# DarkESC.net
KiCad netlist of a schematic drawn in EAGLE
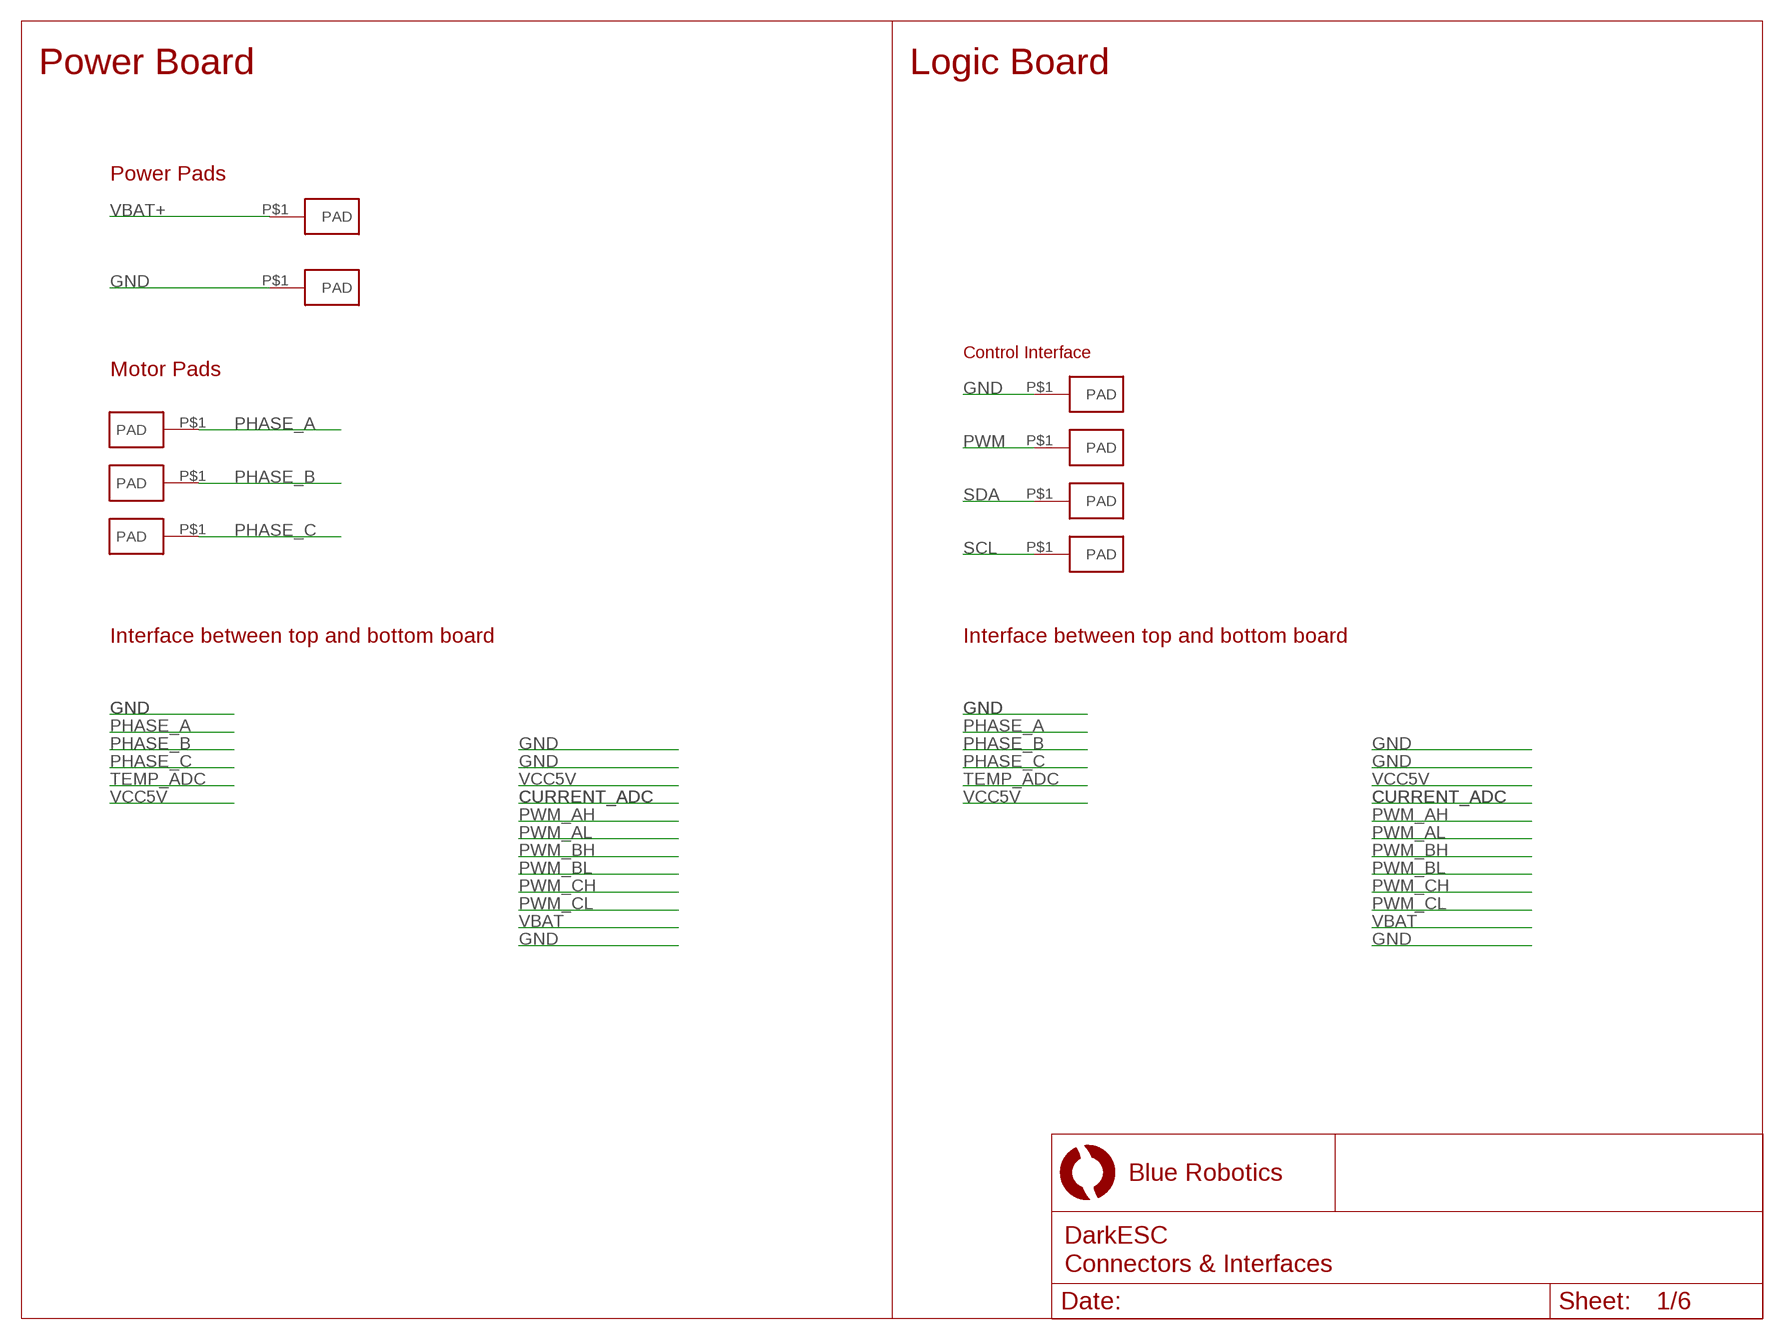
[diagram p0: schematic, sheet 1]
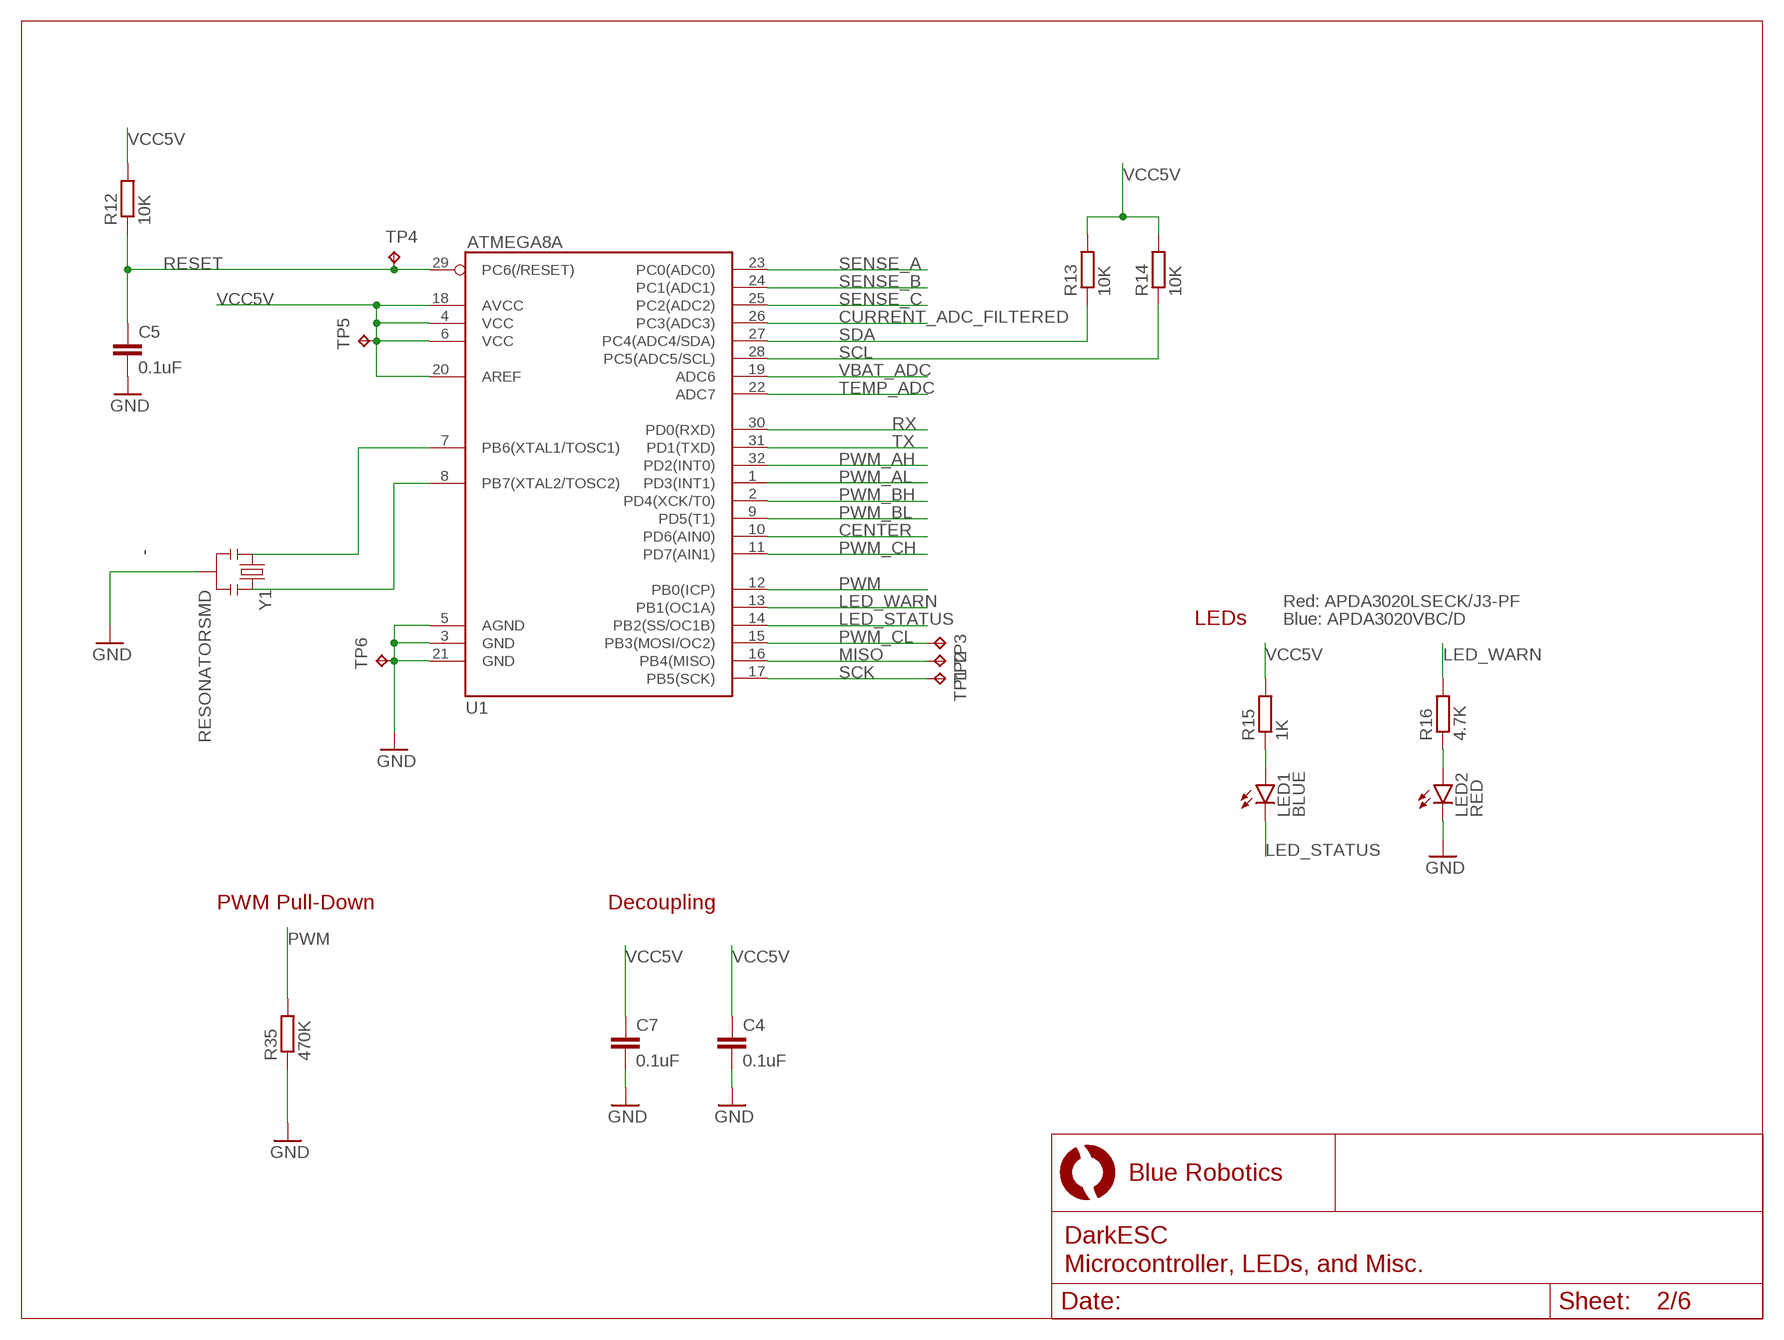
[diagram p1: schematic, sheet 2]
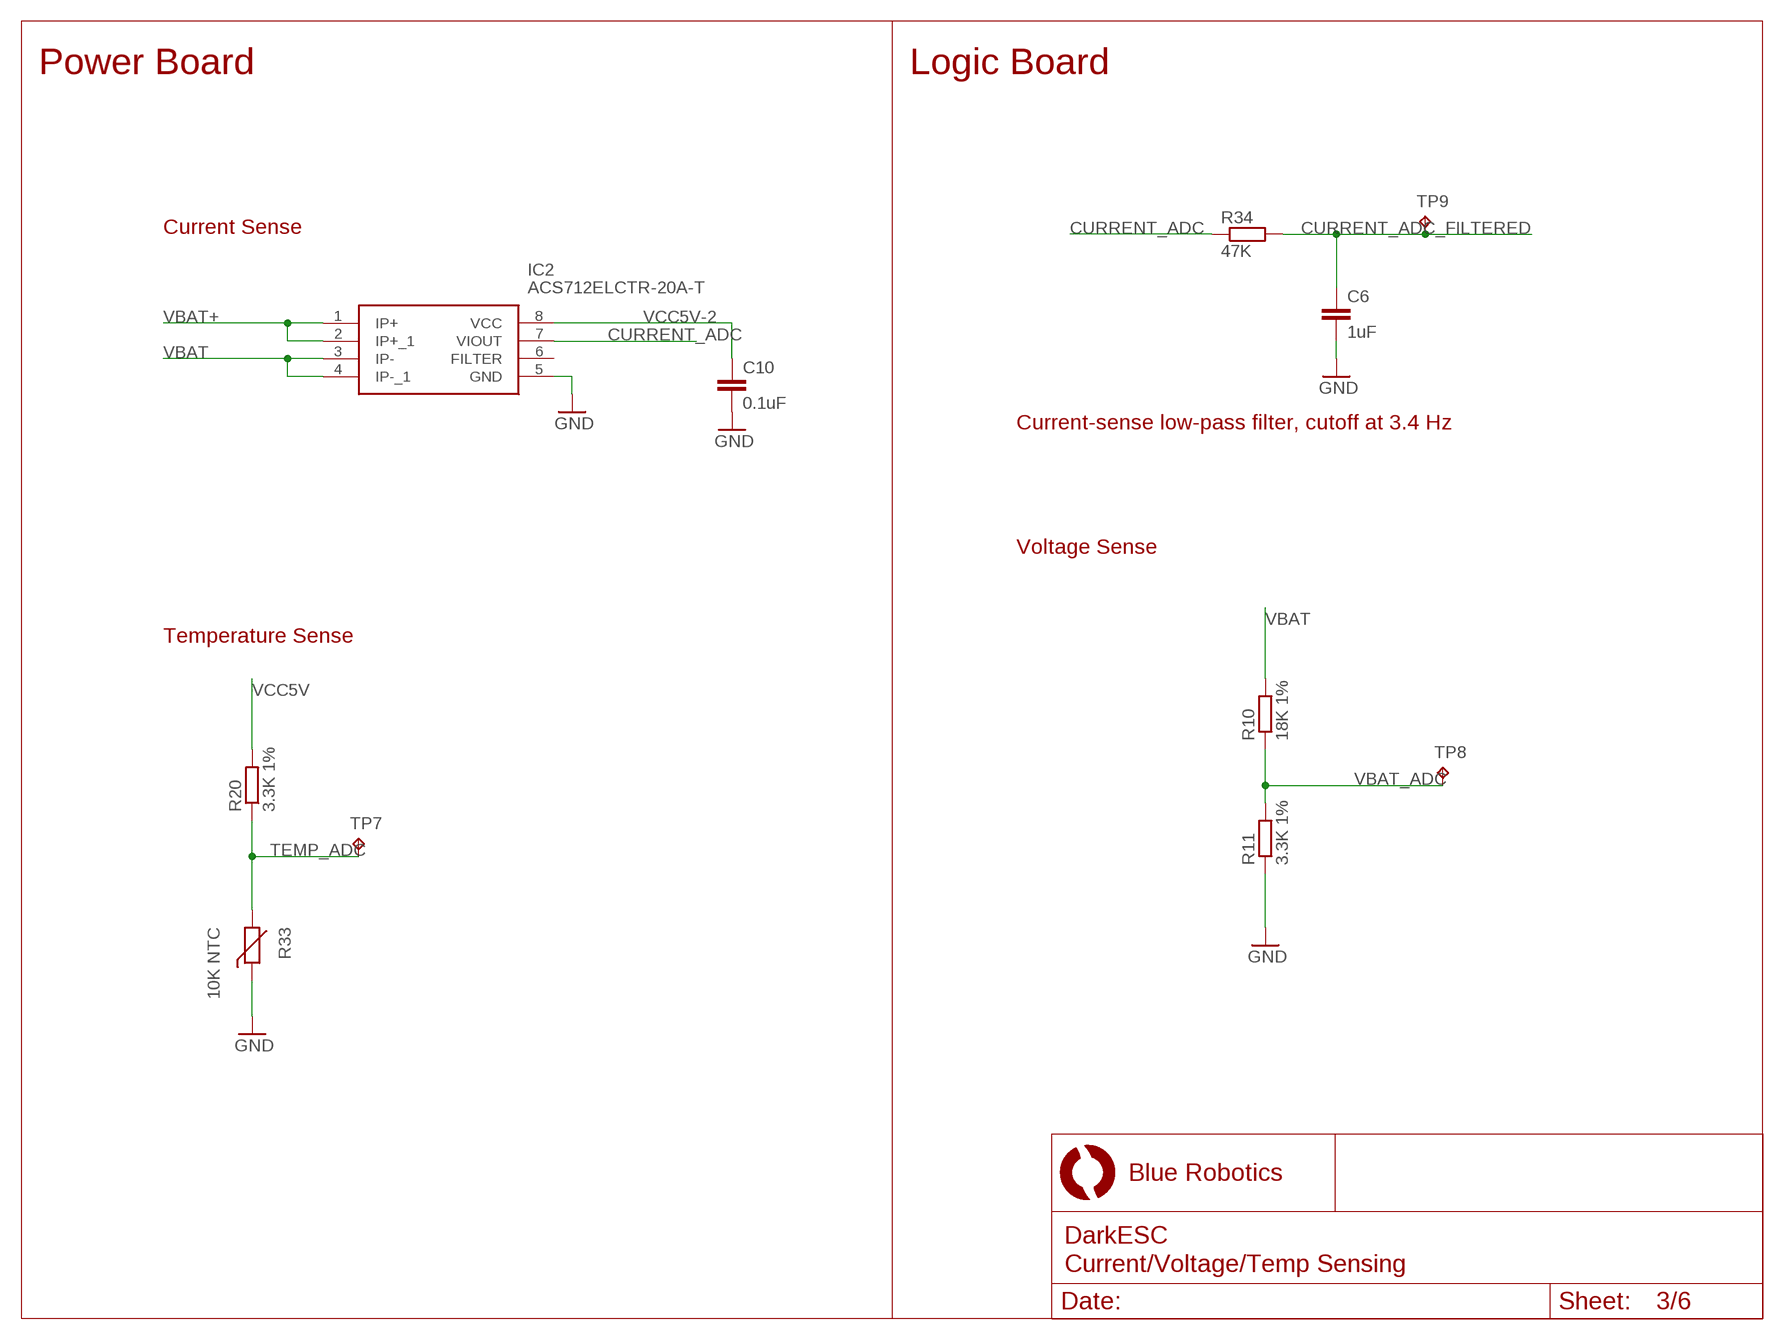
[diagram p2: schematic, sheet 3]
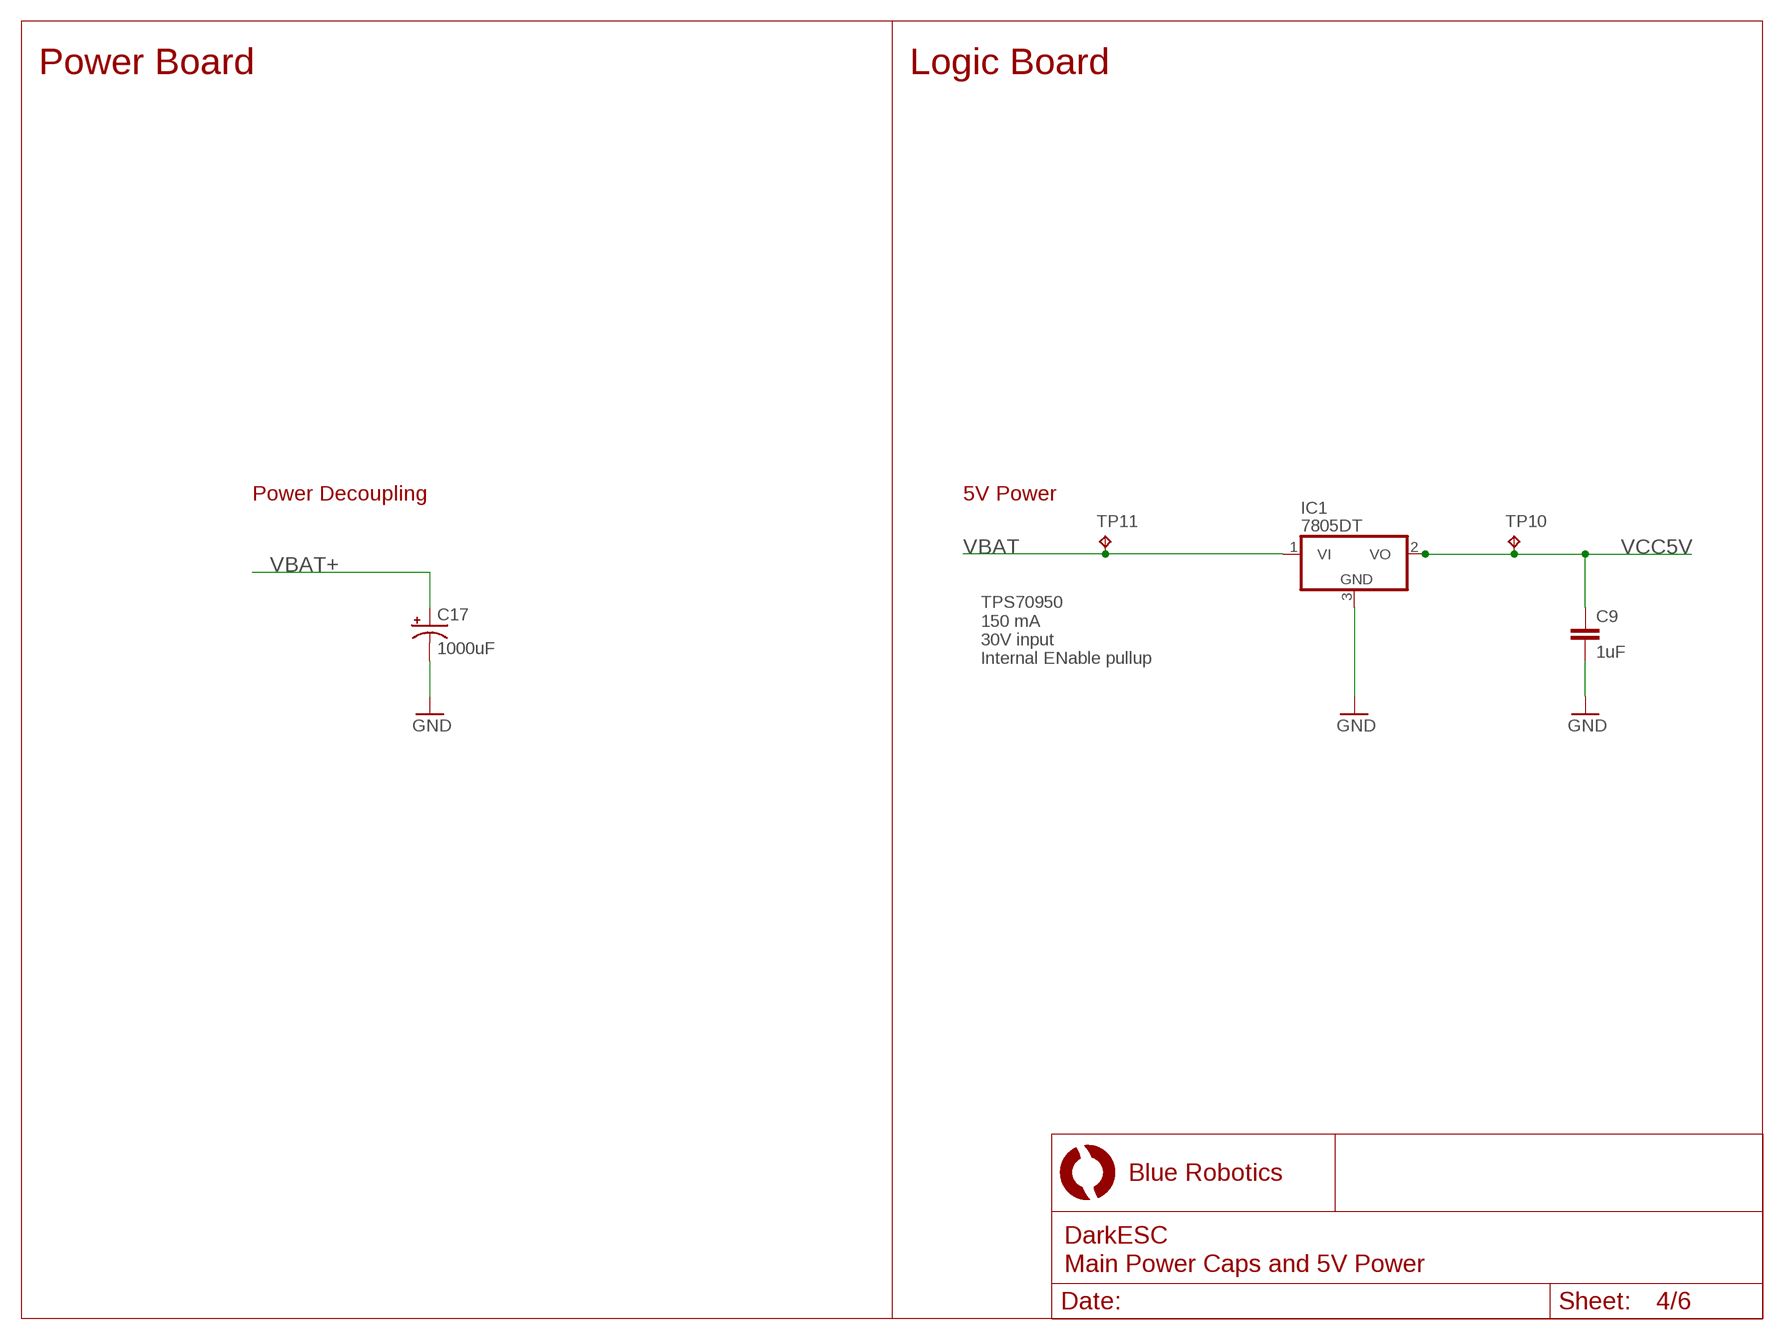
[diagram p3: schematic, sheet 4]
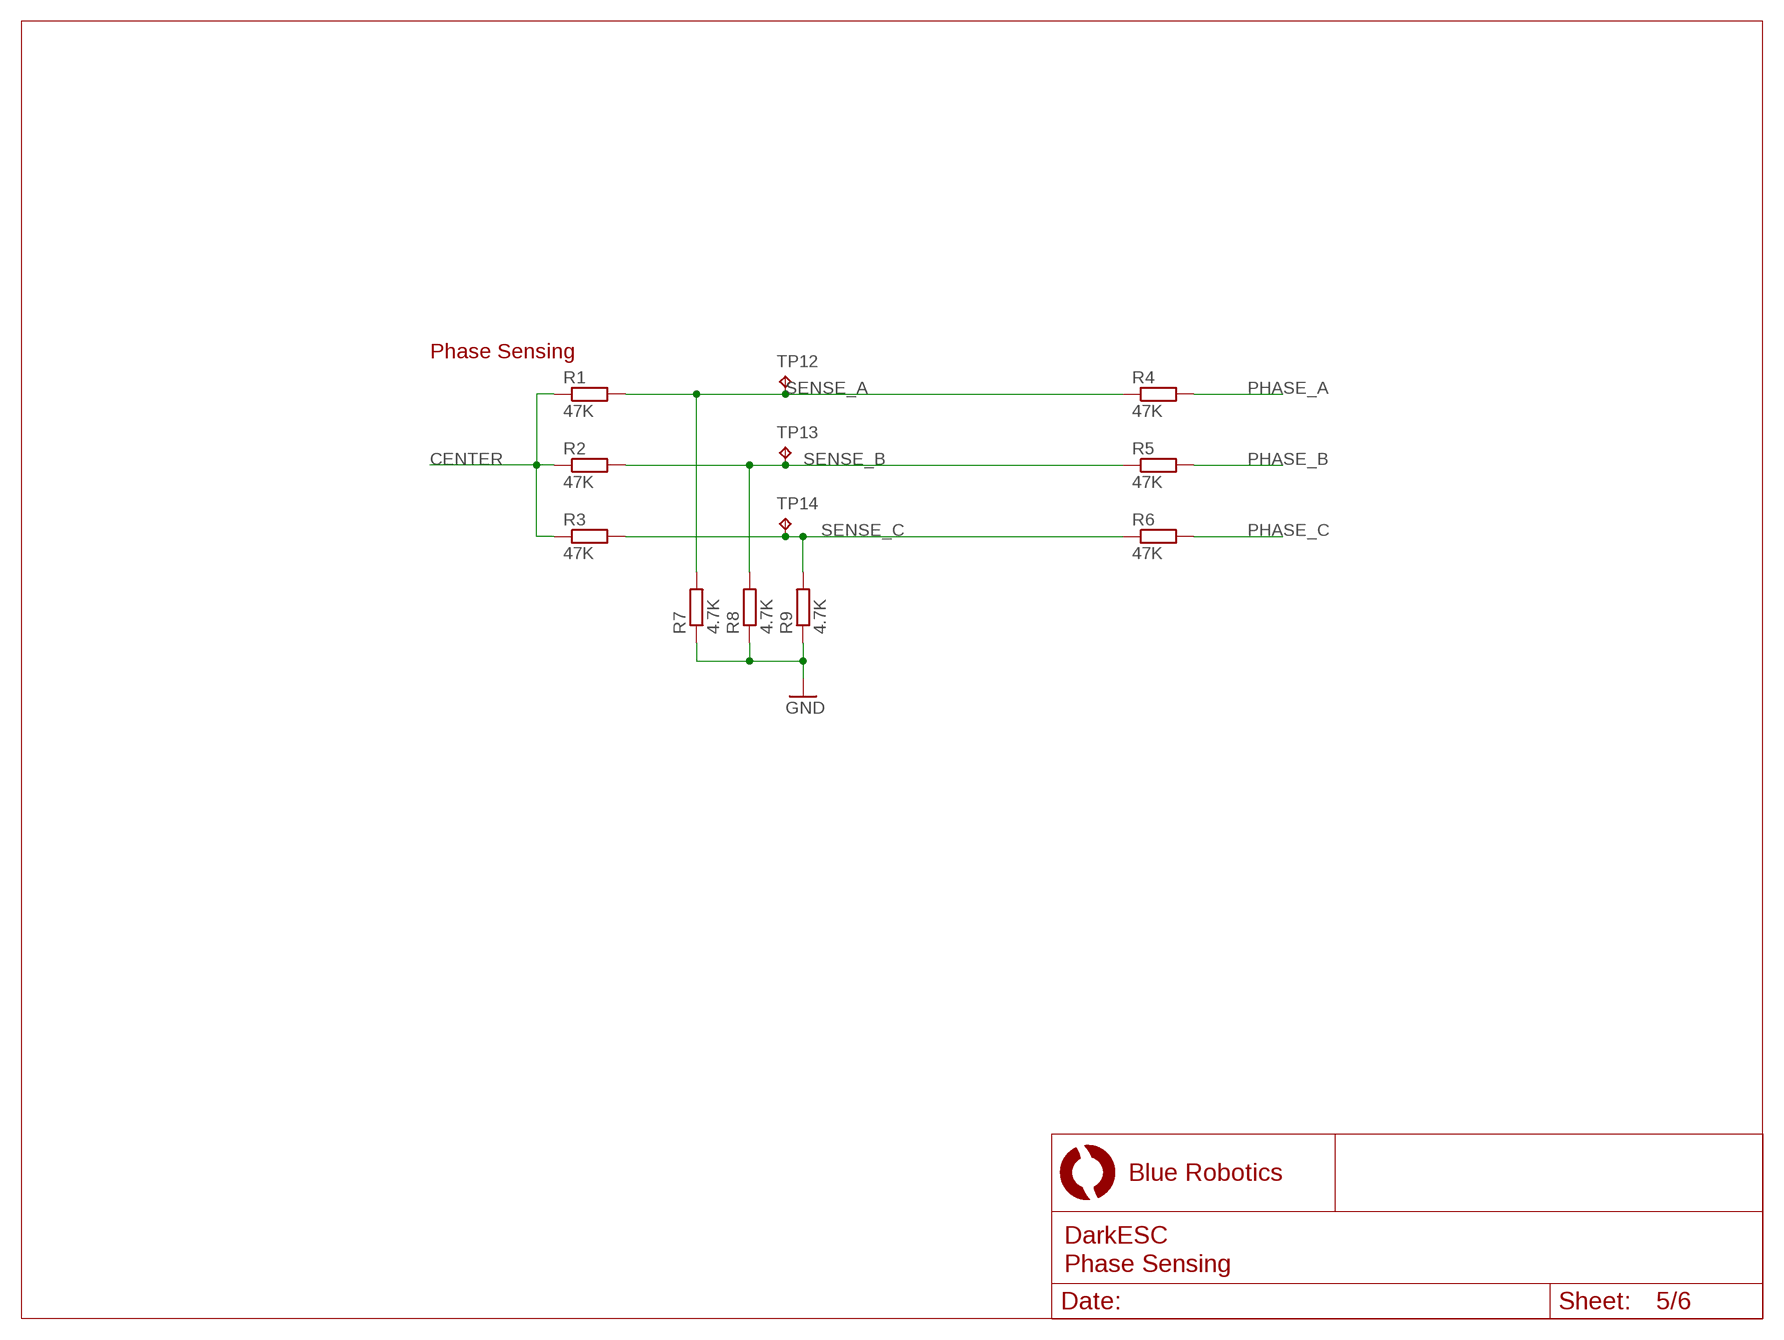
[diagram p4: schematic, sheet 5]
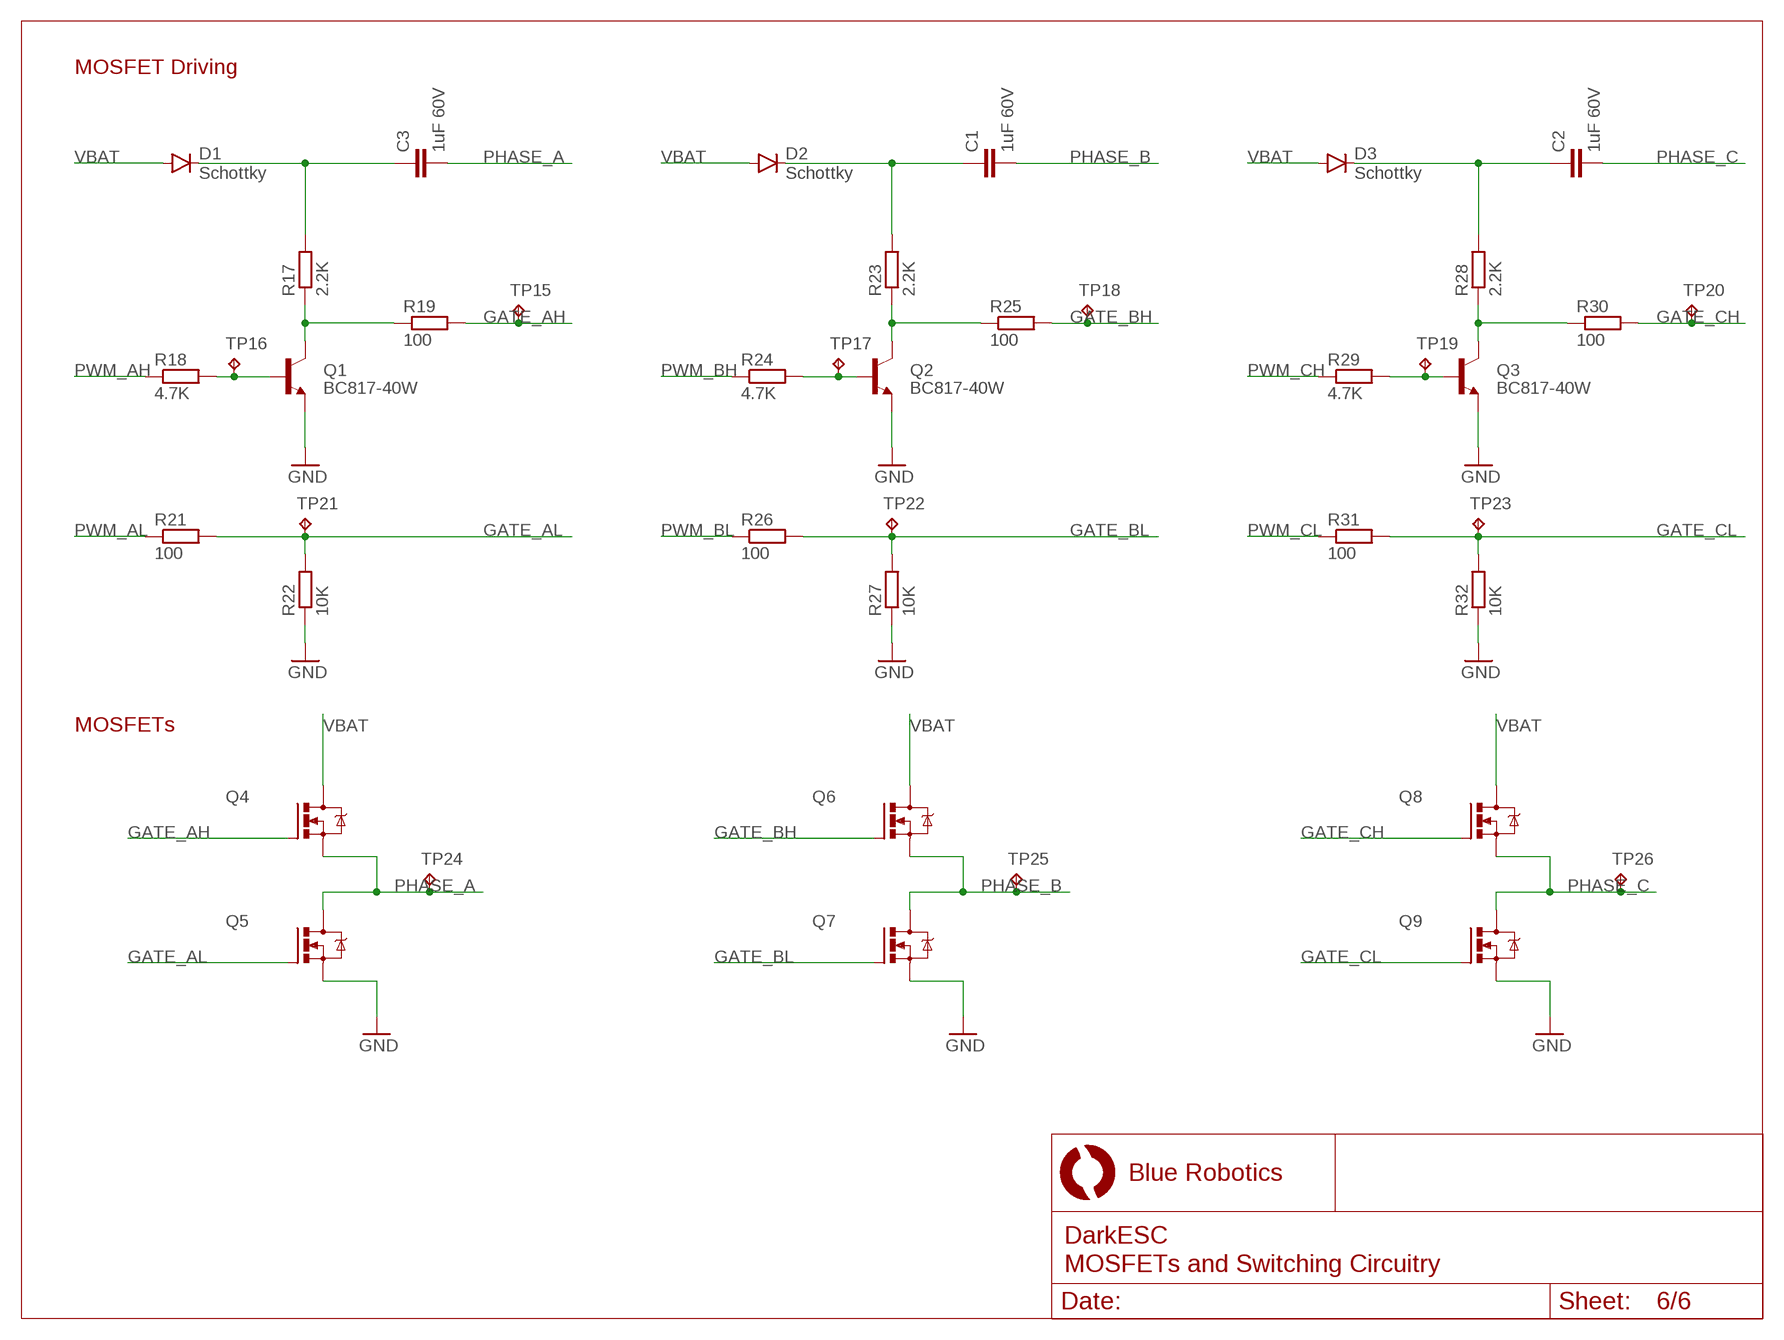
[diagram p5: schematic, sheet 6]

(export (version "E")
  (design (tool "Eeschema 10.0.6"))
  (components
    (comp (ref "C6")
      (value "1uF")
      (footprint "eagle-import:C3216")
      (libsource (lib "eagle-import") (part "C-EUC3216"))
    )
    (comp (ref "C10")
      (value "0.1uF")
      (footprint "eagle-import:C3216")
      (libsource (lib "eagle-import") (part "C-EUC3216"))
    )
    (comp (ref "IC2")
      (value "ACS712ELCTR-20A-T")
      (footprint "eagle-import:SOIC127P600X175-8N")
      (fields (field (name "RS_PART_NUMBER") "1729271"))
      (libsource (lib "eagle-import") (part "ACS712ELCTR-20A-T"))
    )
    (comp (ref "R10")
      (value "18K 1%")
      (footprint "eagle-import:0204_7")
      (libsource (lib "eagle-import") (part "R-EU_0204/7"))
    )
    (comp (ref "R11")
      (value "3.3K 1%")
      (footprint "eagle-import:0204_7")
      (libsource (lib "eagle-import") (part "R-EU_0204/7"))
    )
    (comp (ref "R20")
      (value "3.3K 1%")
      (footprint "eagle-import:0204_7")
      (libsource (lib "eagle-import") (part "R-EU_0204/7"))
    )
    (comp (ref "R33")
      (value "10K NTC")
      (footprint "eagle-import:RS-2,5")
      (libsource (lib "eagle-import") (part "THERMISTOR-2,5"))
    )
    (comp (ref "R34")
      (value "47K")
      (footprint "eagle-import:R3216")
      (libsource (lib "eagle-import") (part "R-EU_R3216"))
    )
    (comp (ref "TP7")
      (value "TPB1,27")
      (footprint "eagle-import:B1,27")
      (libsource (lib "eagle-import") (part "TPB1,27"))
    )
    (comp (ref "TP8")
      (value "TPB1,27")
      (footprint "eagle-import:B1,27")
      (libsource (lib "eagle-import") (part "TPB1,27"))
    )
    (comp (ref "TP9")
      (value "TPB1,27")
      (footprint "eagle-import:B1,27")
      (libsource (lib "eagle-import") (part "TPB1,27"))
    )
    (comp (ref "U$1")
      (value "PADPTH-MED")
      (footprint "eagle-import:PAD-PTH-MED-1")
      (libsource (lib "eagle-import") (part "PADPTH-MED"))
    )
    (comp (ref "U$2")
      (value "PADPTH-MED")
      (footprint "eagle-import:PAD-PTH-MED-1")
      (libsource (lib "eagle-import") (part "PADPTH-MED"))
    )
    (comp (ref "U$5")
      (value "PAD18AWG")
      (footprint "eagle-import:PAD-PTH-18AWG-1")
      (libsource (lib "eagle-import") (part "PAD18AWG"))
    )
    (comp (ref "U$6")
      (value "PAD18AWG")
      (footprint "eagle-import:PAD-PTH-18AWG-1")
      (libsource (lib "eagle-import") (part "PAD18AWG"))
    )
    (comp (ref "U$7")
      (value "PAD18AWG")
      (footprint "eagle-import:PAD-PTH-18AWG-1")
      (libsource (lib "eagle-import") (part "PAD18AWG"))
    )
    (comp (ref "U$11")
      (value "PAD1.5X3MM")
      (footprint "eagle-import:PAD-1.5X3MM")
      (libsource (lib "eagle-import") (part "PAD1.5X3MM"))
    )
    (comp (ref "U$12")
      (value "PAD1.5X3MM")
      (footprint "eagle-import:PAD-1.5X3MM")
      (libsource (lib "eagle-import") (part "PAD1.5X3MM"))
    )
    (comp (ref "U$13")
      (value "PAD1.5X3MM")
      (footprint "eagle-import:PAD-1.5X3MM")
      (libsource (lib "eagle-import") (part "PAD1.5X3MM"))
    )
    (comp (ref "U$14")
      (value "PAD1.5X3MM")
      (footprint "eagle-import:PAD-1.5X3MM")
      (libsource (lib "eagle-import") (part "PAD1.5X3MM"))
    )
    (comp (ref "C9")
      (value "1uF")
      (footprint "eagle-import:C3216")
      (libsource (lib "eagle-import") (part "C-EUC3216"))
    )
    (comp (ref "C17")
      (value "1000uF")
      (footprint "eagle-import:CPOL-RADIAL-100UF-25V")
      (libsource (lib "eagle-import") (part "CAP_POLPTH1"))
    )
    (comp (ref "IC1")
      (value "7805DT")
      (footprint "eagle-import:TO252")
      (libsource (lib "eagle-import") (part "78DT05"))
    )
    (comp (ref "TP10")
      (value "TPB1,27")
      (footprint "eagle-import:B1,27")
      (libsource (lib "eagle-import") (part "TPB1,27"))
    )
    (comp (ref "TP11")
      (value "TPB1,27")
      (footprint "eagle-import:B1,27")
      (libsource (lib "eagle-import") (part "TPB1,27"))
    )
    (comp (ref "R1")
      (value "47K")
      (footprint "eagle-import:R3216")
      (libsource (lib "eagle-import") (part "R-EU_R3216"))
    )
    (comp (ref "R2")
      (value "47K")
      (footprint "eagle-import:R3216")
      (libsource (lib "eagle-import") (part "R-EU_R3216"))
    )
    (comp (ref "R3")
      (value "47K")
      (footprint "eagle-import:R3216")
      (libsource (lib "eagle-import") (part "R-EU_R3216"))
    )
    (comp (ref "R4")
      (value "47K")
      (footprint "eagle-import:R3216")
      (libsource (lib "eagle-import") (part "R-EU_R3216"))
    )
    (comp (ref "R5")
      (value "47K")
      (footprint "eagle-import:R3216")
      (libsource (lib "eagle-import") (part "R-EU_R3216"))
    )
    (comp (ref "R6")
      (value "47K")
      (footprint "eagle-import:R3216")
      (libsource (lib "eagle-import") (part "R-EU_R3216"))
    )
    (comp (ref "R7")
      (value "4.7K")
      (footprint "eagle-import:R3216")
      (libsource (lib "eagle-import") (part "R-EU_R3216"))
    )
    (comp (ref "R8")
      (value "4.7K")
      (footprint "eagle-import:R3216")
      (libsource (lib "eagle-import") (part "R-EU_R3216"))
    )
    (comp (ref "R9")
      (value "4.7K")
      (footprint "eagle-import:R3216")
      (libsource (lib "eagle-import") (part "R-EU_R3216"))
    )
    (comp (ref "TP12")
      (value "TPB1,27")
      (footprint "eagle-import:B1,27")
      (libsource (lib "eagle-import") (part "TPB1,27"))
    )
    (comp (ref "TP13")
      (value "TPB1,27")
      (footprint "eagle-import:B1,27")
      (libsource (lib "eagle-import") (part "TPB1,27"))
    )
    (comp (ref "TP14")
      (value "TPB1,27")
      (footprint "eagle-import:B1,27")
      (libsource (lib "eagle-import") (part "TPB1,27"))
    )
    (comp (ref "C4")
      (value "0.1uF")
      (footprint "eagle-import:C3216")
      (libsource (lib "eagle-import") (part "C-EUC3216"))
    )
    (comp (ref "C5")
      (value "0.1uF")
      (footprint "eagle-import:C3216")
      (libsource (lib "eagle-import") (part "C-EUC3216"))
    )
    (comp (ref "C7")
      (value "0.1uF")
      (footprint "eagle-import:C3216")
      (libsource (lib "eagle-import") (part "C-EUC3216"))
    )
    (comp (ref "LED1")
      (value "BLUE")
      (footprint "eagle-import:SMT-LED-3X2-RA")
      (libsource (lib "eagle-import") (part "LED3X2-RA"))
    )
    (comp (ref "LED2")
      (value "RED")
      (footprint "eagle-import:SMT-LED-3X2-RA")
      (libsource (lib "eagle-import") (part "LED3X2-RA"))
    )
    (comp (ref "R12")
      (value "10K")
      (footprint "eagle-import:R3216")
      (libsource (lib "eagle-import") (part "R-EU_R3216"))
    )
    (comp (ref "R13")
      (value "10K")
      (footprint "eagle-import:R3216")
      (libsource (lib "eagle-import") (part "R-EU_R3216"))
    )
    (comp (ref "R14")
      (value "10K")
      (footprint "eagle-import:R3216")
      (libsource (lib "eagle-import") (part "R-EU_R3216"))
    )
    (comp (ref "R15")
      (value "1K")
      (footprint "eagle-import:R3216")
      (libsource (lib "eagle-import") (part "R-EU_R3216"))
    )
    (comp (ref "R16")
      (value "4.7K")
      (footprint "eagle-import:R3216")
      (libsource (lib "eagle-import") (part "R-EU_R3216"))
    )
    (comp (ref "R35")
      (value "470K")
      (footprint "eagle-import:R3216")
      (libsource (lib "eagle-import") (part "R-EU_R3216"))
    )
    (comp (ref "TP1")
      (value "TPB1,27")
      (footprint "eagle-import:B1,27")
      (libsource (lib "eagle-import") (part "TPB1,27"))
    )
    (comp (ref "TP2")
      (value "TPB1,27")
      (footprint "eagle-import:B1,27")
      (libsource (lib "eagle-import") (part "TPB1,27"))
    )
    (comp (ref "TP3")
      (value "TPB1,27")
      (footprint "eagle-import:B1,27")
      (libsource (lib "eagle-import") (part "TPB1,27"))
    )
    (comp (ref "TP4")
      (value "TPB1,27")
      (footprint "eagle-import:B1,27")
      (libsource (lib "eagle-import") (part "TPB1,27"))
    )
    (comp (ref "TP5")
      (value "TPB1,27")
      (footprint "eagle-import:B1,27")
      (libsource (lib "eagle-import") (part "TPB1,27"))
    )
    (comp (ref "TP6")
      (value "TPB1,27")
      (footprint "eagle-import:B1,27")
      (libsource (lib "eagle-import") (part "TPB1,27"))
    )
    (comp (ref "U1")
      (value "ATMEGA168")
      (footprint "eagle-import:TQFP32-08")
      (libsource (lib "eagle-import") (part "ATMEGA168"))
    )
    (comp (ref "Y1")
      (value "RESONATORSMD")
      (footprint "eagle-import:RESONATOR-SMD")
      (libsource (lib "eagle-import") (part "RESONATORSMD"))
    )
    (comp (ref "C1")
      (value "1uF 60V")
      (footprint "eagle-import:C3216")
      (libsource (lib "eagle-import") (part "C-EUC3216"))
    )
    (comp (ref "C2")
      (value "1uF 60V")
      (footprint "eagle-import:C3216")
      (libsource (lib "eagle-import") (part "C-EUC3216"))
    )
    (comp (ref "C3")
      (value "1uF 60V")
      (footprint "eagle-import:C3216")
      (libsource (lib "eagle-import") (part "C-EUC3216"))
    )
    (comp (ref "D1")
      (value "Schottky")
      (footprint "eagle-import:SMB-DIODE")
      (libsource (lib "eagle-import") (part "DIODESMB"))
    )
    (comp (ref "D2")
      (value "Schottky")
      (footprint "eagle-import:SMB-DIODE")
      (libsource (lib "eagle-import") (part "DIODESMB"))
    )
    (comp (ref "D3")
      (value "Schottky")
      (footprint "eagle-import:SMB-DIODE")
      (libsource (lib "eagle-import") (part "DIODESMB"))
    )
    (comp (ref "Q1")
      (value "BC817-40W")
      (footprint "eagle-import:SOT23")
      (libsource (lib "eagle-import") (part "TRANSISTOR_NPNSOT23"))
    )
    (comp (ref "Q2")
      (value "BC817-40W")
      (footprint "eagle-import:SOT23")
      (libsource (lib "eagle-import") (part "TRANSISTOR_NPNSOT23"))
    )
    (comp (ref "Q3")
      (value "BC817-40W")
      (footprint "eagle-import:SOT23")
      (libsource (lib "eagle-import") (part "TRANSISTOR_NPNSOT23"))
    )
    (comp (ref "Q4")
      (value "IRF520")
      (footprint "eagle-import:TO220BV")
      (libsource (lib "eagle-import") (part "IRF520"))
    )
    (comp (ref "Q5")
      (value "IRF520")
      (footprint "eagle-import:TO220BV")
      (libsource (lib "eagle-import") (part "IRF520"))
    )
    (comp (ref "Q6")
      (value "IRF520")
      (footprint "eagle-import:TO220BV")
      (libsource (lib "eagle-import") (part "IRF520"))
    )
    (comp (ref "Q7")
      (value "IRF520")
      (footprint "eagle-import:TO220BV")
      (libsource (lib "eagle-import") (part "IRF520"))
    )
    (comp (ref "Q8")
      (value "IRF520")
      (footprint "eagle-import:TO220BV")
      (libsource (lib "eagle-import") (part "IRF520"))
    )
    (comp (ref "Q9")
      (value "IRF520")
      (footprint "eagle-import:TO220BV")
      (libsource (lib "eagle-import") (part "IRF520"))
    )
    (comp (ref "R17")
      (value "2.2K")
      (footprint "eagle-import:R3216")
      (libsource (lib "eagle-import") (part "R-EU_R3216"))
    )
    (comp (ref "R18")
      (value "4.7K")
      (footprint "eagle-import:R3216")
      (libsource (lib "eagle-import") (part "R-EU_R3216"))
    )
    (comp (ref "R19")
      (value "100")
      (footprint "eagle-import:R3216")
      (libsource (lib "eagle-import") (part "R-EU_R3216"))
    )
    (comp (ref "R21")
      (value "100")
      (footprint "eagle-import:R3216")
      (libsource (lib "eagle-import") (part "R-EU_R3216"))
    )
    (comp (ref "R22")
      (value "10K")
      (footprint "eagle-import:R3216")
      (libsource (lib "eagle-import") (part "R-EU_R3216"))
    )
    (comp (ref "R23")
      (value "2.2K")
      (footprint "eagle-import:R3216")
      (libsource (lib "eagle-import") (part "R-EU_R3216"))
    )
    (comp (ref "R24")
      (value "4.7K")
      (footprint "eagle-import:R3216")
      (libsource (lib "eagle-import") (part "R-EU_R3216"))
    )
    (comp (ref "R25")
      (value "100")
      (footprint "eagle-import:R3216")
      (libsource (lib "eagle-import") (part "R-EU_R3216"))
    )
    (comp (ref "R26")
      (value "100")
      (footprint "eagle-import:R3216")
      (libsource (lib "eagle-import") (part "R-EU_R3216"))
    )
    (comp (ref "R27")
      (value "10K")
      (footprint "eagle-import:R3216")
      (libsource (lib "eagle-import") (part "R-EU_R3216"))
    )
    (comp (ref "R28")
      (value "2.2K")
      (footprint "eagle-import:R3216")
      (libsource (lib "eagle-import") (part "R-EU_R3216"))
    )
    (comp (ref "R29")
      (value "4.7K")
      (footprint "eagle-import:R3216")
      (libsource (lib "eagle-import") (part "R-EU_R3216"))
    )
    (comp (ref "R30")
      (value "100")
      (footprint "eagle-import:R3216")
      (libsource (lib "eagle-import") (part "R-EU_R3216"))
    )
    (comp (ref "R31")
      (value "100")
      (footprint "eagle-import:R3216")
      (libsource (lib "eagle-import") (part "R-EU_R3216"))
    )
    (comp (ref "R32")
      (value "10K")
      (footprint "eagle-import:R3216")
      (libsource (lib "eagle-import") (part "R-EU_R3216"))
    )
    (comp (ref "TP15")
      (value "TPB1,27")
      (footprint "eagle-import:B1,27")
      (libsource (lib "eagle-import") (part "TPB1,27"))
    )
    (comp (ref "TP16")
      (value "TPB1,27")
      (footprint "eagle-import:B1,27")
      (libsource (lib "eagle-import") (part "TPB1,27"))
    )
    (comp (ref "TP17")
      (value "TPB1,27")
      (footprint "eagle-import:B1,27")
      (libsource (lib "eagle-import") (part "TPB1,27"))
    )
    (comp (ref "TP18")
      (value "TPB1,27")
      (footprint "eagle-import:B1,27")
      (libsource (lib "eagle-import") (part "TPB1,27"))
    )
    (comp (ref "TP19")
      (value "TPB1,27")
      (footprint "eagle-import:B1,27")
      (libsource (lib "eagle-import") (part "TPB1,27"))
    )
    (comp (ref "TP20")
      (value "TPB1,27")
      (footprint "eagle-import:B1,27")
      (libsource (lib "eagle-import") (part "TPB1,27"))
    )
    (comp (ref "TP21")
      (value "TPB1,27")
      (footprint "eagle-import:B1,27")
      (libsource (lib "eagle-import") (part "TPB1,27"))
    )
    (comp (ref "TP22")
      (value "TPB1,27")
      (footprint "eagle-import:B1,27")
      (libsource (lib "eagle-import") (part "TPB1,27"))
    )
    (comp (ref "TP23")
      (value "TPB1,27")
      (footprint "eagle-import:B1,27")
      (libsource (lib "eagle-import") (part "TPB1,27"))
    )
    (comp (ref "TP24")
      (value "TPB1,27")
      (footprint "eagle-import:B1,27")
      (libsource (lib "eagle-import") (part "TPB1,27"))
    )
    (comp (ref "TP25")
      (value "TPB1,27")
      (footprint "eagle-import:B1,27")
      (libsource (lib "eagle-import") (part "TPB1,27"))
    )
    (comp (ref "TP26")
      (value "TPB1,27")
      (footprint "eagle-import:B1,27")
      (libsource (lib "eagle-import") (part "TPB1,27"))
    )
  )
  (nets
    (net (code "1") (name "CENTER") (class "Default")
      (node (ref "R1") (pin "1") (pinfunction "1_1") (pintype "passive"))
      (node (ref "R2") (pin "1") (pinfunction "1_1") (pintype "passive"))
      (node (ref "R3") (pin "1") (pinfunction "1_1") (pintype "passive"))
      (node (ref "U1") (pin "10") (pinfunction "PD6(AIN0)_10") (pintype "bidirectional"))
    )
    (net (code "2") (name "CURRENT_ADC") (class "Default")
      (node (ref "IC2") (pin "7") (pinfunction "VIOUT_7") (pintype "bidirectional"))
      (node (ref "R34") (pin "1") (pinfunction "1_1") (pintype "passive"))
    )
    (net (code "3") (name "CURRENT_ADC_FILTERED") (class "Default")
      (node (ref "C6") (pin "1") (pinfunction "1_1") (pintype "passive"))
      (node (ref "R34") (pin "2") (pinfunction "2_2") (pintype "passive"))
      (node (ref "TP9") (pin "TP") (pinfunction "TP_TP") (pintype "input"))
      (node (ref "U1") (pin "26") (pinfunction "PC3(ADC3)_26") (pintype "bidirectional"))
    )
    (net (code "4") (name "GATE_AH") (class "Default")
      (node (ref "Q4") (pin "G") (pinfunction "G_G") (pintype "passive"))
      (node (ref "R19") (pin "2") (pinfunction "2_2") (pintype "passive"))
      (node (ref "TP15") (pin "TP") (pinfunction "TP_TP") (pintype "input"))
    )
    (net (code "5") (name "GATE_AL") (class "Default")
      (node (ref "Q5") (pin "G") (pinfunction "G_G") (pintype "passive"))
      (node (ref "R21") (pin "2") (pinfunction "2_2") (pintype "passive"))
      (node (ref "R22") (pin "2") (pinfunction "2_2") (pintype "passive"))
      (node (ref "TP21") (pin "TP") (pinfunction "TP_TP") (pintype "input"))
    )
    (net (code "6") (name "GATE_BH") (class "Default")
      (node (ref "Q6") (pin "G") (pinfunction "G_G") (pintype "passive"))
      (node (ref "R25") (pin "2") (pinfunction "2_2") (pintype "passive"))
      (node (ref "TP18") (pin "TP") (pinfunction "TP_TP") (pintype "input"))
    )
    (net (code "7") (name "GATE_BL") (class "Default")
      (node (ref "Q7") (pin "G") (pinfunction "G_G") (pintype "passive"))
      (node (ref "R26") (pin "2") (pinfunction "2_2") (pintype "passive"))
      (node (ref "R27") (pin "2") (pinfunction "2_2") (pintype "passive"))
      (node (ref "TP22") (pin "TP") (pinfunction "TP_TP") (pintype "input"))
    )
    (net (code "8") (name "GATE_CH") (class "Default")
      (node (ref "Q8") (pin "G") (pinfunction "G_G") (pintype "passive"))
      (node (ref "R30") (pin "2") (pinfunction "2_2") (pintype "passive"))
      (node (ref "TP20") (pin "TP") (pinfunction "TP_TP") (pintype "input"))
    )
    (net (code "9") (name "GATE_CL") (class "Default")
      (node (ref "Q9") (pin "G") (pinfunction "G_G") (pintype "passive"))
      (node (ref "R31") (pin "2") (pinfunction "2_2") (pintype "passive"))
      (node (ref "R32") (pin "2") (pinfunction "2_2") (pintype "passive"))
      (node (ref "TP23") (pin "TP") (pinfunction "TP_TP") (pintype "input"))
    )
    (net (code "10") (name "GND") (class "Default")
      (node (ref "C10") (pin "2") (pinfunction "2_2") (pintype "passive"))
      (node (ref "C17") (pin "2") (pinfunction "-_2") (pintype "passive"))
      (node (ref "C4") (pin "2") (pinfunction "2_2") (pintype "passive"))
      (node (ref "C5") (pin "2") (pinfunction "2_2") (pintype "passive"))
      (node (ref "C6") (pin "2") (pinfunction "2_2") (pintype "passive"))
      (node (ref "C7") (pin "2") (pinfunction "2_2") (pintype "passive"))
      (node (ref "C9") (pin "2") (pinfunction "2_2") (pintype "passive"))
      (node (ref "IC1") (pin "3") (pinfunction "GND_3") (pintype "passive"))
      (node (ref "IC2") (pin "5") (pinfunction "GND_5") (pintype "power_in"))
      (node (ref "LED2") (pin "2") (pinfunction "C_2") (pintype "passive"))
      (node (ref "Q1") (pin "2") (pinfunction "E_2") (pintype "passive"))
      (node (ref "Q2") (pin "2") (pinfunction "E_2") (pintype "passive"))
      (node (ref "Q3") (pin "2") (pinfunction "E_2") (pintype "passive"))
      (node (ref "Q5") (pin "S") (pinfunction "S_S") (pintype "passive"))
      (node (ref "Q7") (pin "S") (pinfunction "S_S") (pintype "passive"))
      (node (ref "Q9") (pin "S") (pinfunction "S_S") (pintype "passive"))
      (node (ref "R11") (pin "1") (pinfunction "1_1") (pintype "passive"))
      (node (ref "R22") (pin "1") (pinfunction "1_1") (pintype "passive"))
      (node (ref "R27") (pin "1") (pinfunction "1_1") (pintype "passive"))
      (node (ref "R32") (pin "1") (pinfunction "1_1") (pintype "passive"))
      (node (ref "R33") (pin "1") (pinfunction "1_1") (pintype "passive"))
      (node (ref "R35") (pin "1") (pinfunction "1_1") (pintype "passive"))
      (node (ref "R7") (pin "1") (pinfunction "1_1") (pintype "passive"))
      (node (ref "R8") (pin "1") (pinfunction "1_1") (pintype "passive"))
      (node (ref "R9") (pin "1") (pinfunction "1_1") (pintype "passive"))
      (node (ref "TP6") (pin "TP") (pinfunction "TP_TP") (pintype "input"))
      (node (ref "U$11") (pin "P$1") (pinfunction "PAD_P$1") (pintype "bidirectional"))
      (node (ref "U$2") (pin "P$1") (pinfunction "PAD_P$1") (pintype "bidirectional"))
      (node (ref "U1") (pin "21") (pinfunction "GND_21") (pintype "bidirectional"))
      (node (ref "U1") (pin "3") (pinfunction "GND_3") (pintype "bidirectional"))
      (node (ref "U1") (pin "5") (pinfunction "AGND_5") (pintype "bidirectional"))
      (node (ref "Y1") (pin "2") (pinfunction "2_2") (pintype "passive"))
    )
    (net (code "11") (name "LED_STATUS") (class "Default")
      (node (ref "LED1") (pin "2") (pinfunction "C_2") (pintype "passive"))
      (node (ref "U1") (pin "14") (pinfunction "PB2(SS/OC1B)_14") (pintype "bidirectional"))
    )
    (net (code "12") (name "LED_WARN") (class "Default")
      (node (ref "R16") (pin "2") (pinfunction "2_2") (pintype "passive"))
      (node (ref "U1") (pin "13") (pinfunction "PB1(OC1A)_13") (pintype "bidirectional"))
    )
    (net (code "13") (name "MISO") (class "Default")
      (node (ref "TP2") (pin "TP") (pinfunction "TP_TP") (pintype "input"))
      (node (ref "U1") (pin "16") (pinfunction "PB4(MISO)_16") (pintype "bidirectional"))
    )
    (net (code "14") (name "Net-(C1-Pad1)") (class "Default")
      (node (ref "C1") (pin "1") (pinfunction "1_1") (pintype "passive"))
      (node (ref "D2") (pin "C") (pinfunction "C_C") (pintype "passive"))
      (node (ref "R23") (pin "2") (pinfunction "2_2") (pintype "passive"))
    )
    (net (code "15") (name "Net-(C2-Pad1)") (class "Default")
      (node (ref "C2") (pin "1") (pinfunction "1_1") (pintype "passive"))
      (node (ref "D3") (pin "C") (pinfunction "C_C") (pintype "passive"))
      (node (ref "R28") (pin "2") (pinfunction "2_2") (pintype "passive"))
    )
    (net (code "16") (name "Net-(C3-Pad1)") (class "Default")
      (node (ref "C3") (pin "1") (pinfunction "1_1") (pintype "passive"))
      (node (ref "D1") (pin "C") (pinfunction "C_C") (pintype "passive"))
      (node (ref "R17") (pin "2") (pinfunction "2_2") (pintype "passive"))
    )
    (net (code "17") (name "Net-(LED1-A)") (class "Default")
      (node (ref "LED1") (pin "1") (pinfunction "A_1") (pintype "passive"))
      (node (ref "R15") (pin "1") (pinfunction "1_1") (pintype "passive"))
    )
    (net (code "18") (name "Net-(LED2-A)") (class "Default")
      (node (ref "LED2") (pin "1") (pinfunction "A_1") (pintype "passive"))
      (node (ref "R16") (pin "1") (pinfunction "1_1") (pintype "passive"))
    )
    (net (code "19") (name "Net-(Q1-B)") (class "Default")
      (node (ref "Q1") (pin "1") (pinfunction "B_1") (pintype "passive"))
      (node (ref "R18") (pin "2") (pinfunction "2_2") (pintype "passive"))
      (node (ref "TP16") (pin "TP") (pinfunction "TP_TP") (pintype "input"))
    )
    (net (code "20") (name "Net-(Q1-C)") (class "Default")
      (node (ref "Q1") (pin "3") (pinfunction "C_3") (pintype "passive"))
      (node (ref "R17") (pin "1") (pinfunction "1_1") (pintype "passive"))
      (node (ref "R19") (pin "1") (pinfunction "1_1") (pintype "passive"))
    )
    (net (code "21") (name "Net-(Q2-B)") (class "Default")
      (node (ref "Q2") (pin "1") (pinfunction "B_1") (pintype "passive"))
      (node (ref "R24") (pin "2") (pinfunction "2_2") (pintype "passive"))
      (node (ref "TP17") (pin "TP") (pinfunction "TP_TP") (pintype "input"))
    )
    (net (code "22") (name "Net-(Q2-C)") (class "Default")
      (node (ref "Q2") (pin "3") (pinfunction "C_3") (pintype "passive"))
      (node (ref "R23") (pin "1") (pinfunction "1_1") (pintype "passive"))
      (node (ref "R25") (pin "1") (pinfunction "1_1") (pintype "passive"))
    )
    (net (code "23") (name "Net-(Q3-B)") (class "Default")
      (node (ref "Q3") (pin "1") (pinfunction "B_1") (pintype "passive"))
      (node (ref "R29") (pin "2") (pinfunction "2_2") (pintype "passive"))
      (node (ref "TP19") (pin "TP") (pinfunction "TP_TP") (pintype "input"))
    )
    (net (code "24") (name "Net-(Q3-C)") (class "Default")
      (node (ref "Q3") (pin "3") (pinfunction "C_3") (pintype "passive"))
      (node (ref "R28") (pin "1") (pinfunction "1_1") (pintype "passive"))
      (node (ref "R30") (pin "1") (pinfunction "1_1") (pintype "passive"))
    )
    (net (code "25") (name "Net-(U1-PB6(XTAL1{slash}TOSC1))") (class "Default")
      (node (ref "U1") (pin "7") (pinfunction "PB6(XTAL1/TOSC1)_7") (pintype "bidirectional"))
      (node (ref "Y1") (pin "1") (pinfunction "1_1") (pintype "passive"))
    )
    (net (code "26") (name "Net-(U1-PB7(XTAL2{slash}TOSC2))") (class "Default")
      (node (ref "U1") (pin "8") (pinfunction "PB7(XTAL2/TOSC2)_8") (pintype "bidirectional"))
      (node (ref "Y1") (pin "3") (pinfunction "3_3") (pintype "passive"))
    )
    (net (code "27") (name "PHASE_A") (class "Default")
      (node (ref "C3") (pin "2") (pinfunction "2_2") (pintype "passive"))
      (node (ref "Q4") (pin "S") (pinfunction "S_S") (pintype "passive"))
      (node (ref "Q5") (pin "D") (pinfunction "D_D") (pintype "passive"))
      (node (ref "R4") (pin "2") (pinfunction "2_2") (pintype "passive"))
      (node (ref "TP24") (pin "TP") (pinfunction "TP_TP") (pintype "input"))
      (node (ref "U$5") (pin "P$1") (pinfunction "PAD_P$1") (pintype "bidirectional"))
    )
    (net (code "28") (name "PHASE_B") (class "Default")
      (node (ref "C1") (pin "2") (pinfunction "2_2") (pintype "passive"))
      (node (ref "Q6") (pin "S") (pinfunction "S_S") (pintype "passive"))
      (node (ref "Q7") (pin "D") (pinfunction "D_D") (pintype "passive"))
      (node (ref "R5") (pin "2") (pinfunction "2_2") (pintype "passive"))
      (node (ref "TP25") (pin "TP") (pinfunction "TP_TP") (pintype "input"))
      (node (ref "U$6") (pin "P$1") (pinfunction "PAD_P$1") (pintype "bidirectional"))
    )
    (net (code "29") (name "PHASE_C") (class "Default")
      (node (ref "C2") (pin "2") (pinfunction "2_2") (pintype "passive"))
      (node (ref "Q8") (pin "S") (pinfunction "S_S") (pintype "passive"))
      (node (ref "Q9") (pin "D") (pinfunction "D_D") (pintype "passive"))
      (node (ref "R6") (pin "2") (pinfunction "2_2") (pintype "passive"))
      (node (ref "TP26") (pin "TP") (pinfunction "TP_TP") (pintype "input"))
      (node (ref "U$7") (pin "P$1") (pinfunction "PAD_P$1") (pintype "bidirectional"))
    )
    (net (code "30") (name "PWM") (class "Default")
      (node (ref "R35") (pin "2") (pinfunction "2_2") (pintype "passive"))
      (node (ref "U$14") (pin "P$1") (pinfunction "PAD_P$1") (pintype "bidirectional"))
      (node (ref "U1") (pin "12") (pinfunction "PB0(ICP)_12") (pintype "bidirectional"))
    )
    (net (code "31") (name "PWM_AH") (class "Default")
      (node (ref "R18") (pin "1") (pinfunction "1_1") (pintype "passive"))
      (node (ref "U1") (pin "32") (pinfunction "PD2(INT0)_32") (pintype "bidirectional"))
    )
    (net (code "32") (name "PWM_AL") (class "Default")
      (node (ref "R21") (pin "1") (pinfunction "1_1") (pintype "passive"))
      (node (ref "U1") (pin "1") (pinfunction "PD3(INT1)_1") (pintype "bidirectional"))
    )
    (net (code "33") (name "PWM_BH") (class "Default")
      (node (ref "R24") (pin "1") (pinfunction "1_1") (pintype "passive"))
      (node (ref "U1") (pin "2") (pinfunction "PD4(XCK/T0)_2") (pintype "bidirectional"))
    )
    (net (code "34") (name "PWM_BL") (class "Default")
      (node (ref "R26") (pin "1") (pinfunction "1_1") (pintype "passive"))
      (node (ref "U1") (pin "9") (pinfunction "PD5(T1)_9") (pintype "bidirectional"))
    )
    (net (code "35") (name "PWM_CH") (class "Default")
      (node (ref "R29") (pin "1") (pinfunction "1_1") (pintype "passive"))
      (node (ref "U1") (pin "11") (pinfunction "PD7(AIN1)_11") (pintype "bidirectional"))
    )
    (net (code "36") (name "PWM_CL") (class "Default")
      (node (ref "R31") (pin "1") (pinfunction "1_1") (pintype "passive"))
      (node (ref "TP3") (pin "TP") (pinfunction "TP_TP") (pintype "input"))
      (node (ref "U1") (pin "15") (pinfunction "PB3(MOSI/OC2)_15") (pintype "bidirectional"))
    )
    (net (code "37") (name "RESET") (class "Default")
      (node (ref "C5") (pin "1") (pinfunction "1_1") (pintype "passive"))
      (node (ref "R12") (pin "1") (pinfunction "1_1") (pintype "passive"))
      (node (ref "TP4") (pin "TP") (pinfunction "TP_TP") (pintype "input"))
      (node (ref "U1") (pin "29") (pinfunction "PC6(/RESET)_29") (pintype "bidirectional"))
    )
    (net (code "38") (name "RX") (class "Default")
      (node (ref "U1") (pin "30") (pinfunction "PD0(RXD)_30") (pintype "bidirectional"))
    )
    (net (code "39") (name "SCK") (class "Default")
      (node (ref "TP1") (pin "TP") (pinfunction "TP_TP") (pintype "input"))
      (node (ref "U1") (pin "17") (pinfunction "PB5(SCK)_17") (pintype "bidirectional"))
    )
    (net (code "40") (name "SCL") (class "Default")
      (node (ref "R14") (pin "1") (pinfunction "1_1") (pintype "passive"))
      (node (ref "U$13") (pin "P$1") (pinfunction "PAD_P$1") (pintype "bidirectional"))
      (node (ref "U1") (pin "28") (pinfunction "PC5(ADC5/SCL)_28") (pintype "bidirectional"))
    )
    (net (code "41") (name "SDA") (class "Default")
      (node (ref "R13") (pin "1") (pinfunction "1_1") (pintype "passive"))
      (node (ref "U$12") (pin "P$1") (pinfunction "PAD_P$1") (pintype "bidirectional"))
      (node (ref "U1") (pin "27") (pinfunction "PC4(ADC4/SDA)_27") (pintype "bidirectional"))
    )
    (net (code "42") (name "SENSE_A") (class "Default")
      (node (ref "R1") (pin "2") (pinfunction "2_2") (pintype "passive"))
      (node (ref "R4") (pin "1") (pinfunction "1_1") (pintype "passive"))
      (node (ref "R7") (pin "2") (pinfunction "2_2") (pintype "passive"))
      (node (ref "TP12") (pin "TP") (pinfunction "TP_TP") (pintype "input"))
      (node (ref "U1") (pin "23") (pinfunction "PC0(ADC0)_23") (pintype "bidirectional"))
    )
    (net (code "43") (name "SENSE_B") (class "Default")
      (node (ref "R2") (pin "2") (pinfunction "2_2") (pintype "passive"))
      (node (ref "R5") (pin "1") (pinfunction "1_1") (pintype "passive"))
      (node (ref "R8") (pin "2") (pinfunction "2_2") (pintype "passive"))
      (node (ref "TP13") (pin "TP") (pinfunction "TP_TP") (pintype "input"))
      (node (ref "U1") (pin "24") (pinfunction "PC1(ADC1)_24") (pintype "bidirectional"))
    )
    (net (code "44") (name "SENSE_C") (class "Default")
      (node (ref "R3") (pin "2") (pinfunction "2_2") (pintype "passive"))
      (node (ref "R6") (pin "1") (pinfunction "1_1") (pintype "passive"))
      (node (ref "R9") (pin "2") (pinfunction "2_2") (pintype "passive"))
      (node (ref "TP14") (pin "TP") (pinfunction "TP_TP") (pintype "input"))
      (node (ref "U1") (pin "25") (pinfunction "PC2(ADC2)_25") (pintype "bidirectional"))
    )
    (net (code "45") (name "TEMP_ADC") (class "Default")
      (node (ref "R20") (pin "1") (pinfunction "1_1") (pintype "passive"))
      (node (ref "R33") (pin "2") (pinfunction "2_2") (pintype "passive"))
      (node (ref "TP7") (pin "TP") (pinfunction "TP_TP") (pintype "input"))
      (node (ref "U1") (pin "22") (pinfunction "ADC7_22") (pintype "bidirectional"))
    )
    (net (code "46") (name "TX") (class "Default")
      (node (ref "U1") (pin "31") (pinfunction "PD1(TXD)_31") (pintype "bidirectional"))
    )
    (net (code "47") (name "VBAT") (class "Default")
      (node (ref "D1") (pin "A") (pinfunction "A_A") (pintype "passive"))
      (node (ref "D2") (pin "A") (pinfunction "A_A") (pintype "passive"))
      (node (ref "D3") (pin "A") (pinfunction "A_A") (pintype "passive"))
      (node (ref "IC1") (pin "1") (pinfunction "VI_1") (pintype "input"))
      (node (ref "IC2") (pin "3") (pinfunction "IP-_3") (pintype "bidirectional"))
      (node (ref "IC2") (pin "4") (pinfunction "IP-_1_4") (pintype "bidirectional"))
      (node (ref "Q4") (pin "D") (pinfunction "D_D") (pintype "passive"))
      (node (ref "Q6") (pin "D") (pinfunction "D_D") (pintype "passive"))
      (node (ref "Q8") (pin "D") (pinfunction "D_D") (pintype "passive"))
      (node (ref "R10") (pin "2") (pinfunction "2_2") (pintype "passive"))
      (node (ref "TP11") (pin "TP") (pinfunction "TP_TP") (pintype "input"))
    )
    (net (code "48") (name "VBAT+") (class "Default")
      (node (ref "C17") (pin "1") (pinfunction "+_1") (pintype "passive"))
      (node (ref "IC2") (pin "1") (pinfunction "IP+_1") (pintype "bidirectional"))
      (node (ref "IC2") (pin "2") (pinfunction "IP+_1_2") (pintype "bidirectional"))
      (node (ref "U$1") (pin "P$1") (pinfunction "PAD_P$1") (pintype "bidirectional"))
    )
    (net (code "49") (name "VBAT_ADC") (class "Default")
      (node (ref "R10") (pin "1") (pinfunction "1_1") (pintype "passive"))
      (node (ref "R11") (pin "2") (pinfunction "2_2") (pintype "passive"))
      (node (ref "TP8") (pin "TP") (pinfunction "TP_TP") (pintype "input"))
      (node (ref "U1") (pin "19") (pinfunction "ADC6_19") (pintype "bidirectional"))
    )
    (net (code "50") (name "VCC5V") (class "Default")
      (node (ref "C4") (pin "1") (pinfunction "1_1") (pintype "passive"))
      (node (ref "C7") (pin "1") (pinfunction "1_1") (pintype "passive"))
      (node (ref "C9") (pin "1") (pinfunction "1_1") (pintype "passive"))
      (node (ref "IC1") (pin "2") (pinfunction "VO_2") (pintype "passive"))
      (node (ref "R12") (pin "2") (pinfunction "2_2") (pintype "passive"))
      (node (ref "R13") (pin "2") (pinfunction "2_2") (pintype "passive"))
      (node (ref "R14") (pin "2") (pinfunction "2_2") (pintype "passive"))
      (node (ref "R15") (pin "2") (pinfunction "2_2") (pintype "passive"))
      (node (ref "R20") (pin "2") (pinfunction "2_2") (pintype "passive"))
      (node (ref "TP10") (pin "TP") (pinfunction "TP_TP") (pintype "input"))
      (node (ref "TP5") (pin "TP") (pinfunction "TP_TP") (pintype "input"))
      (node (ref "U1") (pin "18") (pinfunction "AVCC_18") (pintype "bidirectional"))
      (node (ref "U1") (pin "20") (pinfunction "AREF_20") (pintype "bidirectional"))
      (node (ref "U1") (pin "4") (pinfunction "VCC_4") (pintype "bidirectional"))
      (node (ref "U1") (pin "6") (pinfunction "VCC_6") (pintype "bidirectional"))
    )
    (net (code "51") (name "VCC5V-2") (class "Default")
      (node (ref "C10") (pin "1") (pinfunction "1_1") (pintype "passive"))
      (node (ref "IC2") (pin "8") (pinfunction "VCC_8") (pintype "power_in"))
    )
    (net (code "52") (name "unconnected-(IC2-FILTER-Pad6)") (class "Default")
      (node (ref "IC2") (pin "6") (pinfunction "FILTER_6") (pintype "bidirectional"))
    )
  )
)
